# 07_LMS7002M_1_Power.net
KiCad netlist of a schematic drawn in Altium Designer
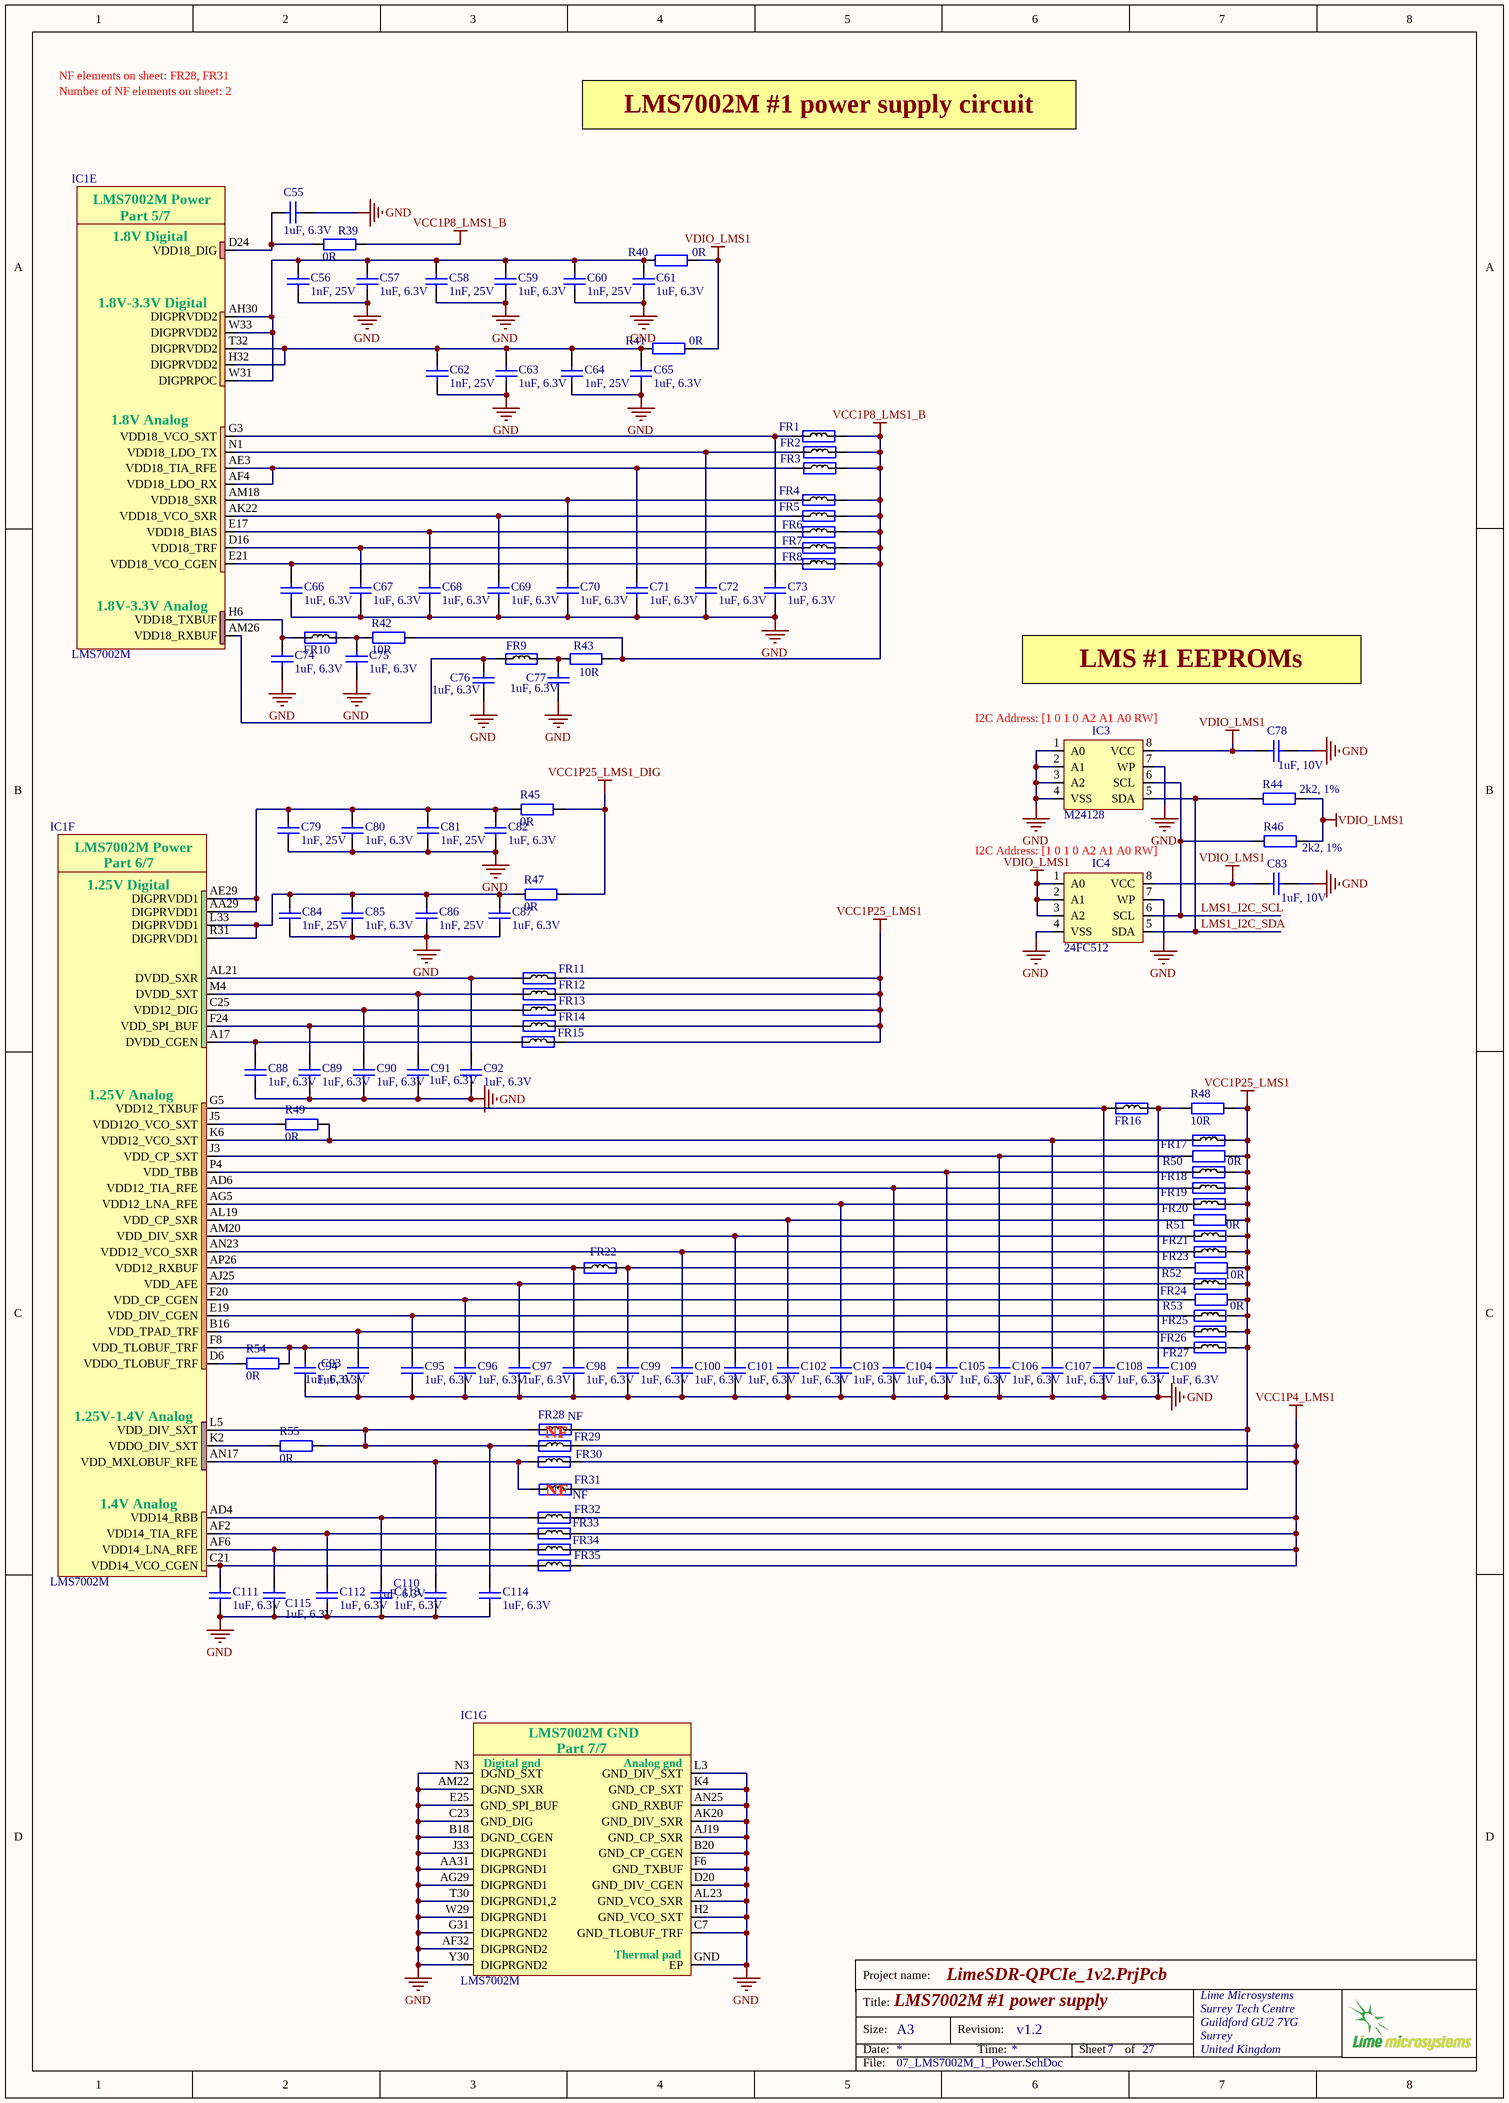
[diagram p0: 07_LMS7002M_1_Power.SchDoc]

(export (version "E")
  (design (tool "Eeschema 10.0.6"))
  (components
    (comp (ref "C55")
      (value "1uF, 6.3V")
      (footprint "CAP0201")
      (fields (field (name "TOLERANCE") "±20%") (field (name "MANUFACTURER") "TDK Corporation"))
      (libsource (lib "LimeMicroAltiumLib_schLib") (part "Cap_0402"))
    )
    (comp (ref "C56")
      (value "1nF, 25V")
      (footprint "CAP0201")
      (fields (field (name "TOLERANCE") "±10%") (field (name "MANUFACTURER") "TDK Corporation"))
      (libsource (lib "LimeMicroAltiumLib_schLib") (part "Cap_0402"))
    )
    (comp (ref "C57")
      (value "1uF, 6.3V")
      (footprint "CAP0201")
      (fields (field (name "TOLERANCE") "±20%") (field (name "MANUFACTURER") "TDK Corporation"))
      (libsource (lib "LimeMicroAltiumLib_schLib") (part "Cap_0402"))
    )
    (comp (ref "C58")
      (value "1nF, 25V")
      (footprint "CAP0201")
      (fields (field (name "TOLERANCE") "±10%") (field (name "MANUFACTURER") "TDK Corporation"))
      (libsource (lib "LimeMicroAltiumLib_schLib") (part "Cap_0402"))
    )
    (comp (ref "C59")
      (value "1uF, 6.3V")
      (footprint "CAP0201")
      (fields (field (name "TOLERANCE") "±20%") (field (name "MANUFACTURER") "TDK Corporation"))
      (libsource (lib "LimeMicroAltiumLib_schLib") (part "Cap_0402"))
    )
    (comp (ref "C60")
      (value "1nF, 25V")
      (footprint "CAP0201")
      (fields (field (name "TOLERANCE") "±10%") (field (name "MANUFACTURER") "TDK Corporation"))
      (libsource (lib "LimeMicroAltiumLib_schLib") (part "Cap_0402"))
    )
    (comp (ref "C61")
      (value "1uF, 6.3V")
      (footprint "CAP0201")
      (fields (field (name "TOLERANCE") "±20%") (field (name "MANUFACTURER") "TDK Corporation"))
      (libsource (lib "LimeMicroAltiumLib_schLib") (part "Cap_0402"))
    )
    (comp (ref "C62")
      (value "1nF, 25V")
      (footprint "CAP0201")
      (fields (field (name "TOLERANCE") "±10%") (field (name "MANUFACTURER") "TDK Corporation"))
      (libsource (lib "LimeMicroAltiumLib_schLib") (part "Cap_0402"))
    )
    (comp (ref "C63")
      (value "1uF, 6.3V")
      (footprint "CAP0201")
      (fields (field (name "TOLERANCE") "±20%") (field (name "MANUFACTURER") "TDK Corporation"))
      (libsource (lib "LimeMicroAltiumLib_schLib") (part "Cap_0402"))
    )
    (comp (ref "C64")
      (value "1nF, 25V")
      (footprint "CAP0201")
      (fields (field (name "TOLERANCE") "±10%") (field (name "MANUFACTURER") "TDK Corporation"))
      (libsource (lib "LimeMicroAltiumLib_schLib") (part "Cap_0402"))
    )
    (comp (ref "C65")
      (value "1uF, 6.3V")
      (footprint "CAP0201")
      (fields (field (name "TOLERANCE") "±20%") (field (name "MANUFACTURER") "TDK Corporation"))
      (libsource (lib "LimeMicroAltiumLib_schLib") (part "Cap_0402"))
    )
    (comp (ref "C66")
      (value "1uF, 6.3V")
      (footprint "CAP0201")
      (fields (field (name "TOLERANCE") "±20%") (field (name "MANUFACTURER") "TDK Corporation"))
      (libsource (lib "LimeMicroAltiumLib_schLib") (part "Cap_0402"))
    )
    (comp (ref "C67")
      (value "1uF, 6.3V")
      (footprint "CAP0201")
      (fields (field (name "TOLERANCE") "±20%") (field (name "MANUFACTURER") "TDK Corporation"))
      (libsource (lib "LimeMicroAltiumLib_schLib") (part "Cap_0402"))
    )
    (comp (ref "C68")
      (value "1uF, 6.3V")
      (footprint "CAP0201")
      (fields (field (name "TOLERANCE") "±20%") (field (name "MANUFACTURER") "TDK Corporation"))
      (libsource (lib "LimeMicroAltiumLib_schLib") (part "Cap_0402"))
    )
    (comp (ref "C69")
      (value "1uF, 6.3V")
      (footprint "CAP0201")
      (fields (field (name "TOLERANCE") "±20%") (field (name "MANUFACTURER") "TDK Corporation"))
      (libsource (lib "LimeMicroAltiumLib_schLib") (part "Cap_0402"))
    )
    (comp (ref "C70")
      (value "1uF, 6.3V")
      (footprint "CAP0201")
      (fields (field (name "TOLERANCE") "±20%") (field (name "MANUFACTURER") "TDK Corporation"))
      (libsource (lib "LimeMicroAltiumLib_schLib") (part "Cap_0402"))
    )
    (comp (ref "C71")
      (value "1uF, 6.3V")
      (footprint "CAP0201")
      (fields (field (name "TOLERANCE") "±20%") (field (name "MANUFACTURER") "TDK Corporation"))
      (libsource (lib "LimeMicroAltiumLib_schLib") (part "Cap_0402"))
    )
    (comp (ref "C72")
      (value "1uF, 6.3V")
      (footprint "CAP0201")
      (fields (field (name "TOLERANCE") "±20%") (field (name "MANUFACTURER") "TDK Corporation"))
      (libsource (lib "LimeMicroAltiumLib_schLib") (part "Cap_0402"))
    )
    (comp (ref "C73")
      (value "1uF, 6.3V")
      (footprint "CAP0201")
      (fields (field (name "TOLERANCE") "±20%") (field (name "MANUFACTURER") "TDK Corporation"))
      (libsource (lib "LimeMicroAltiumLib_schLib") (part "Cap_0402"))
    )
    (comp (ref "C74")
      (value "1uF, 6.3V")
      (footprint "CAP0201")
      (fields (field (name "TOLERANCE") "±20%") (field (name "MANUFACTURER") "TDK Corporation"))
      (libsource (lib "LimeMicroAltiumLib_schLib") (part "Cap_0402"))
    )
    (comp (ref "C75")
      (value "1uF, 6.3V")
      (footprint "CAP0201")
      (fields (field (name "TOLERANCE") "±20%") (field (name "MANUFACTURER") "TDK Corporation"))
      (libsource (lib "LimeMicroAltiumLib_schLib") (part "Cap_0402"))
    )
    (comp (ref "C76")
      (value "1uF, 6.3V")
      (footprint "CAP0201")
      (fields (field (name "TOLERANCE") "±20%") (field (name "MANUFACTURER") "TDK Corporation"))
      (libsource (lib "LimeMicroAltiumLib_schLib") (part "Cap_0402"))
    )
    (comp (ref "C77")
      (value "1uF, 6.3V")
      (footprint "CAP0201")
      (fields (field (name "TOLERANCE") "±20%") (field (name "MANUFACTURER") "TDK Corporation"))
      (libsource (lib "LimeMicroAltiumLib_schLib") (part "Cap_0402"))
    )
    (comp (ref "C78")
      (value "1uF, 10V")
      (footprint "CAP0402")
      (fields (field (name "MANUFACTURER") "TDK"))
      (libsource (lib "LimeMicroAltiumLib_schLib") (part "Cap_0402"))
    )
    (comp (ref "C79")
      (value "1nF, 25V")
      (footprint "CAP0201")
      (fields (field (name "TOLERANCE") "±10%") (field (name "MANUFACTURER") "TDK Corporation"))
      (libsource (lib "LimeMicroAltiumLib_schLib") (part "Cap_0402"))
    )
    (comp (ref "C80")
      (value "1uF, 6.3V")
      (footprint "CAP0201")
      (fields (field (name "TOLERANCE") "±20%") (field (name "MANUFACTURER") "TDK Corporation"))
      (libsource (lib "LimeMicroAltiumLib_schLib") (part "Cap_0402"))
    )
    (comp (ref "C81")
      (value "1nF, 25V")
      (footprint "CAP0201")
      (fields (field (name "TOLERANCE") "±10%") (field (name "MANUFACTURER") "TDK Corporation"))
      (libsource (lib "LimeMicroAltiumLib_schLib") (part "Cap_0402"))
    )
    (comp (ref "C82")
      (value "1uF, 6.3V")
      (footprint "CAP0201")
      (fields (field (name "TOLERANCE") "±20%") (field (name "MANUFACTURER") "TDK Corporation"))
      (libsource (lib "LimeMicroAltiumLib_schLib") (part "Cap_0402"))
    )
    (comp (ref "C83")
      (value "1uF, 10V")
      (footprint "CAP0402")
      (fields (field (name "MANUFACTURER") "TDK"))
      (libsource (lib "LimeMicroAltiumLib_schLib") (part "Cap_0402"))
    )
    (comp (ref "C84")
      (value "1nF, 25V")
      (footprint "CAP0201")
      (fields (field (name "TOLERANCE") "±10%") (field (name "MANUFACTURER") "TDK Corporation"))
      (libsource (lib "LimeMicroAltiumLib_schLib") (part "Cap_0402"))
    )
    (comp (ref "C85")
      (value "1uF, 6.3V")
      (footprint "CAP0201")
      (fields (field (name "TOLERANCE") "±20%") (field (name "MANUFACTURER") "TDK Corporation"))
      (libsource (lib "LimeMicroAltiumLib_schLib") (part "Cap_0402"))
    )
    (comp (ref "C86")
      (value "1nF, 25V")
      (footprint "CAP0201")
      (fields (field (name "TOLERANCE") "±10%") (field (name "MANUFACTURER") "TDK Corporation"))
      (libsource (lib "LimeMicroAltiumLib_schLib") (part "Cap_0402"))
    )
    (comp (ref "C87")
      (value "1uF, 6.3V")
      (footprint "CAP0201")
      (fields (field (name "TOLERANCE") "±20%") (field (name "MANUFACTURER") "TDK Corporation"))
      (libsource (lib "LimeMicroAltiumLib_schLib") (part "Cap_0402"))
    )
    (comp (ref "C88")
      (value "1uF, 6.3V")
      (footprint "CAP0201")
      (fields (field (name "TOLERANCE") "±20%") (field (name "MANUFACTURER") "TDK Corporation"))
      (libsource (lib "LimeMicroAltiumLib_schLib") (part "Cap_0402"))
    )
    (comp (ref "C89")
      (value "1uF, 6.3V")
      (footprint "CAP0201")
      (fields (field (name "TOLERANCE") "±20%") (field (name "MANUFACTURER") "TDK Corporation"))
      (libsource (lib "LimeMicroAltiumLib_schLib") (part "Cap_0402"))
    )
    (comp (ref "C90")
      (value "1uF, 6.3V")
      (footprint "CAP0201")
      (fields (field (name "TOLERANCE") "±20%") (field (name "MANUFACTURER") "TDK Corporation"))
      (libsource (lib "LimeMicroAltiumLib_schLib") (part "Cap_0402"))
    )
    (comp (ref "C91")
      (value "1uF, 6.3V")
      (footprint "CAP0201")
      (fields (field (name "TOLERANCE") "±20%") (field (name "MANUFACTURER") "TDK Corporation"))
      (libsource (lib "LimeMicroAltiumLib_schLib") (part "Cap_0402"))
    )
    (comp (ref "C92")
      (value "1uF, 6.3V")
      (footprint "CAP0201")
      (fields (field (name "TOLERANCE") "±20%") (field (name "MANUFACTURER") "TDK Corporation"))
      (libsource (lib "LimeMicroAltiumLib_schLib") (part "Cap_0402"))
    )
    (comp (ref "C93")
      (value "1uF, 6.3V")
      (footprint "CAP0201")
      (fields (field (name "TOLERANCE") "±20%") (field (name "MANUFACTURER") "TDK Corporation"))
      (libsource (lib "LimeMicroAltiumLib_schLib") (part "Cap_0402"))
    )
    (comp (ref "C94")
      (value "1uF, 6.3V")
      (footprint "CAP0201")
      (fields (field (name "TOLERANCE") "±20%") (field (name "MANUFACTURER") "TDK Corporation"))
      (libsource (lib "LimeMicroAltiumLib_schLib") (part "Cap_0402"))
    )
    (comp (ref "C95")
      (value "1uF, 6.3V")
      (footprint "CAP0201")
      (fields (field (name "TOLERANCE") "±20%") (field (name "MANUFACTURER") "TDK Corporation"))
      (libsource (lib "LimeMicroAltiumLib_schLib") (part "Cap_0402"))
    )
    (comp (ref "C96")
      (value "1uF, 6.3V")
      (footprint "CAP0201")
      (fields (field (name "TOLERANCE") "±20%") (field (name "MANUFACTURER") "TDK Corporation"))
      (libsource (lib "LimeMicroAltiumLib_schLib") (part "Cap_0402"))
    )
    (comp (ref "C97")
      (value "1uF, 6.3V")
      (footprint "CAP0201")
      (fields (field (name "TOLERANCE") "±20%") (field (name "MANUFACTURER") "TDK Corporation"))
      (libsource (lib "LimeMicroAltiumLib_schLib") (part "Cap_0402"))
    )
    (comp (ref "C98")
      (value "1uF, 6.3V")
      (footprint "CAP0201")
      (fields (field (name "TOLERANCE") "±20%") (field (name "MANUFACTURER") "TDK Corporation"))
      (libsource (lib "LimeMicroAltiumLib_schLib") (part "Cap_0402"))
    )
    (comp (ref "C99")
      (value "1uF, 6.3V")
      (footprint "CAP0201")
      (fields (field (name "TOLERANCE") "±20%") (field (name "MANUFACTURER") "TDK Corporation"))
      (libsource (lib "LimeMicroAltiumLib_schLib") (part "Cap_0402"))
    )
    (comp (ref "C100")
      (value "1uF, 6.3V")
      (footprint "CAP0201")
      (fields (field (name "TOLERANCE") "±20%") (field (name "MANUFACTURER") "TDK Corporation"))
      (libsource (lib "LimeMicroAltiumLib_schLib") (part "Cap_0402"))
    )
    (comp (ref "C101")
      (value "1uF, 6.3V")
      (footprint "CAP0201")
      (fields (field (name "TOLERANCE") "±20%") (field (name "MANUFACTURER") "TDK Corporation"))
      (libsource (lib "LimeMicroAltiumLib_schLib") (part "Cap_0402"))
    )
    (comp (ref "C102")
      (value "1uF, 6.3V")
      (footprint "CAP0201")
      (fields (field (name "TOLERANCE") "±20%") (field (name "MANUFACTURER") "TDK Corporation"))
      (libsource (lib "LimeMicroAltiumLib_schLib") (part "Cap_0402"))
    )
    (comp (ref "C103")
      (value "1uF, 6.3V")
      (footprint "CAP0201")
      (fields (field (name "TOLERANCE") "±20%") (field (name "MANUFACTURER") "TDK Corporation"))
      (libsource (lib "LimeMicroAltiumLib_schLib") (part "Cap_0402"))
    )
    (comp (ref "C104")
      (value "1uF, 6.3V")
      (footprint "CAP0201")
      (fields (field (name "TOLERANCE") "±20%") (field (name "MANUFACTURER") "TDK Corporation"))
      (libsource (lib "LimeMicroAltiumLib_schLib") (part "Cap_0402"))
    )
    (comp (ref "C105")
      (value "1uF, 6.3V")
      (footprint "CAP0201")
      (fields (field (name "TOLERANCE") "±20%") (field (name "MANUFACTURER") "TDK Corporation"))
      (libsource (lib "LimeMicroAltiumLib_schLib") (part "Cap_0402"))
    )
    (comp (ref "C106")
      (value "1uF, 6.3V")
      (footprint "CAP0201")
      (fields (field (name "TOLERANCE") "±20%") (field (name "MANUFACTURER") "TDK Corporation"))
      (libsource (lib "LimeMicroAltiumLib_schLib") (part "Cap_0402"))
    )
    (comp (ref "C107")
      (value "1uF, 6.3V")
      (footprint "CAP0201")
      (fields (field (name "TOLERANCE") "±20%") (field (name "MANUFACTURER") "TDK Corporation"))
      (libsource (lib "LimeMicroAltiumLib_schLib") (part "Cap_0402"))
    )
    (comp (ref "C108")
      (value "1uF, 6.3V")
      (footprint "CAP0201")
      (fields (field (name "TOLERANCE") "±20%") (field (name "MANUFACTURER") "TDK Corporation"))
      (libsource (lib "LimeMicroAltiumLib_schLib") (part "Cap_0402"))
    )
    (comp (ref "C109")
      (value "1uF, 6.3V")
      (footprint "CAP0201")
      (fields (field (name "TOLERANCE") "±20%") (field (name "MANUFACTURER") "TDK Corporation"))
      (libsource (lib "LimeMicroAltiumLib_schLib") (part "Cap_0402"))
    )
    (comp (ref "C110")
      (value "1uF, 6.3V")
      (footprint "CAP0201")
      (fields (field (name "TOLERANCE") "±20%") (field (name "MANUFACTURER") "TDK Corporation"))
      (libsource (lib "LimeMicroAltiumLib_schLib") (part "Cap_0402"))
    )
    (comp (ref "C111")
      (value "1uF, 6.3V")
      (footprint "CAP0201")
      (fields (field (name "TOLERANCE") "±20%") (field (name "MANUFACTURER") "TDK Corporation"))
      (libsource (lib "LimeMicroAltiumLib_schLib") (part "Cap_0402"))
    )
    (comp (ref "C112")
      (value "1uF, 6.3V")
      (footprint "CAP0201")
      (fields (field (name "TOLERANCE") "±20%") (field (name "MANUFACTURER") "TDK Corporation"))
      (libsource (lib "LimeMicroAltiumLib_schLib") (part "Cap_0402"))
    )
    (comp (ref "C113")
      (value "1uF, 6.3V")
      (footprint "CAP0201")
      (fields (field (name "TOLERANCE") "±20%") (field (name "MANUFACTURER") "TDK Corporation"))
      (libsource (lib "LimeMicroAltiumLib_schLib") (part "Cap_0402"))
    )
    (comp (ref "C114")
      (value "1uF, 6.3V")
      (footprint "CAP0201")
      (fields (field (name "TOLERANCE") "±20%") (field (name "MANUFACTURER") "TDK Corporation"))
      (libsource (lib "LimeMicroAltiumLib_schLib") (part "Cap_0402"))
    )
    (comp (ref "C115")
      (value "1uF, 6.3V")
      (footprint "CAP0201")
      (fields (field (name "TOLERANCE") "±20%") (field (name "MANUFACTURER") "TDK Corporation"))
      (libsource (lib "LimeMicroAltiumLib_schLib") (part "Cap_0402"))
    )
    (comp (ref "FR1")
      (value "Ferrite")
      (footprint "RES0201")
      (fields (field (name "MANUFACTURER") "Taiyo Yuden"))
      (libsource (lib "") (part "Ferrite_1"))
    )
    (comp (ref "FR2")
      (value "Ferrite")
      (footprint "RES0201")
      (fields (field (name "MANUFACTURER") "Taiyo Yuden"))
      (libsource (lib "LimeMicroAltiumLib_schLib") (part "Ferrite"))
    )
    (comp (ref "FR3")
      (value "Ferrite")
      (footprint "RES0201")
      (fields (field (name "MANUFACTURER") "Taiyo Yuden"))
      (libsource (lib "LimeMicroAltiumLib_schLib") (part "Ferrite"))
    )
    (comp (ref "FR4")
      (value "Ferrite")
      (footprint "RES0201")
      (fields (field (name "MANUFACTURER") "Taiyo Yuden"))
      (libsource (lib "") (part "Ferrite_1"))
    )
    (comp (ref "FR5")
      (value "Ferrite")
      (footprint "RES0201")
      (fields (field (name "MANUFACTURER") "Taiyo Yuden"))
      (libsource (lib "") (part "Ferrite_1"))
    )
    (comp (ref "FR6")
      (value "Ferrite")
      (footprint "RES0201")
      (fields (field (name "MANUFACTURER") "Taiyo Yuden"))
      (libsource (lib "") (part "Ferrite_1"))
    )
    (comp (ref "FR7")
      (value "Ferrite")
      (footprint "RES0201")
      (fields (field (name "MANUFACTURER") "Taiyo Yuden"))
      (libsource (lib "") (part "Ferrite_1"))
    )
    (comp (ref "FR8")
      (value "Ferrite")
      (footprint "RES0201")
      (fields (field (name "MANUFACTURER") "Taiyo Yuden"))
      (libsource (lib "") (part "Ferrite_1"))
    )
    (comp (ref "FR9")
      (value "Ferrite")
      (footprint "RES0201")
      (fields (field (name "MANUFACTURER") "Taiyo Yuden"))
      (libsource (lib "") (part "Ferrite_1"))
    )
    (comp (ref "FR10")
      (value "Ferrite")
      (footprint "RES0201")
      (fields (field (name "MANUFACTURER") "Taiyo Yuden"))
      (libsource (lib "LimeMicroAltiumLib_schLib") (part "Ferrite"))
    )
    (comp (ref "FR11")
      (value "Ferrite")
      (footprint "RES0201")
      (fields (field (name "MANUFACTURER") "Taiyo Yuden"))
      (libsource (lib "LimeMicroAltiumLib_schLib") (part "Ferrite"))
    )
    (comp (ref "FR12")
      (value "Ferrite")
      (footprint "RES0201")
      (fields (field (name "MANUFACTURER") "Taiyo Yuden"))
      (libsource (lib "LimeMicroAltiumLib_schLib") (part "Ferrite"))
    )
    (comp (ref "FR13")
      (value "Ferrite")
      (footprint "RES0201")
      (fields (field (name "MANUFACTURER") "Taiyo Yuden"))
      (libsource (lib "LimeMicroAltiumLib_schLib") (part "Ferrite"))
    )
    (comp (ref "FR14")
      (value "Ferrite")
      (footprint "RES0201")
      (fields (field (name "MANUFACTURER") "Taiyo Yuden"))
      (libsource (lib "LimeMicroAltiumLib_schLib") (part "Ferrite"))
    )
    (comp (ref "FR15")
      (value "Ferrite")
      (footprint "RES0201")
      (fields (field (name "MANUFACTURER") "Taiyo Yuden"))
      (libsource (lib "") (part "Ferrite_1"))
    )
    (comp (ref "FR16")
      (value "Ferrite")
      (footprint "RES0201")
      (fields (field (name "MANUFACTURER") "Taiyo Yuden"))
      (libsource (lib "LimeMicroAltiumLib_schLib") (part "Ferrite"))
    )
    (comp (ref "FR17")
      (value "Ferrite")
      (footprint "RES0201")
      (fields (field (name "MANUFACTURER") "Taiyo Yuden"))
      (libsource (lib "LimeMicroAltiumLib_schLib") (part "Ferrite"))
    )
    (comp (ref "FR18")
      (value "Ferrite")
      (footprint "RES0201")
      (fields (field (name "MANUFACTURER") "Taiyo Yuden"))
      (libsource (lib "LimeMicroAltiumLib_schLib") (part "Ferrite"))
    )
    (comp (ref "FR19")
      (value "Ferrite")
      (footprint "RES0201")
      (fields (field (name "MANUFACTURER") "Taiyo Yuden"))
      (libsource (lib "LimeMicroAltiumLib_schLib") (part "Ferrite"))
    )
    (comp (ref "FR20")
      (value "Ferrite")
      (footprint "RES0201")
      (fields (field (name "MANUFACTURER") "Taiyo Yuden"))
      (libsource (lib "LimeMicroAltiumLib_schLib") (part "Ferrite"))
    )
    (comp (ref "FR21")
      (value "Ferrite")
      (footprint "RES0201")
      (fields (field (name "MANUFACTURER") "Taiyo Yuden"))
      (libsource (lib "") (part "Ferrite_1"))
    )
    (comp (ref "FR22")
      (value "Ferrite")
      (footprint "RES0201")
      (fields (field (name "MANUFACTURER") "Taiyo Yuden"))
      (libsource (lib "") (part "Ferrite_1"))
    )
    (comp (ref "FR23")
      (value "Ferrite")
      (footprint "RES0201")
      (fields (field (name "MANUFACTURER") "Taiyo Yuden"))
      (libsource (lib "") (part "Ferrite_1"))
    )
    (comp (ref "FR24")
      (value "Ferrite")
      (footprint "RES0201")
      (fields (field (name "MANUFACTURER") "Taiyo Yuden"))
      (libsource (lib "") (part "Ferrite_1"))
    )
    (comp (ref "FR25")
      (value "Ferrite")
      (footprint "RES0201")
      (fields (field (name "MANUFACTURER") "Taiyo Yuden"))
      (libsource (lib "") (part "Ferrite_1"))
    )
    (comp (ref "FR26")
      (value "Ferrite")
      (footprint "RES0201")
      (fields (field (name "MANUFACTURER") "Taiyo Yuden"))
      (libsource (lib "") (part "Ferrite_1"))
    )
    (comp (ref "FR27")
      (value "Ferrite")
      (footprint "RES0201")
      (fields (field (name "MANUFACTURER") "Taiyo Yuden"))
      (libsource (lib "") (part "Ferrite_1"))
    )
    (comp (ref "FR28")
      (value "Ferrite")
      (footprint "RES0201")
      (fields (field (name "MANUFACTURER") "Taiyo Yuden") (field (name "ASSEMBLY INFO") "NF"))
      (libsource (lib "LimeMicroAltiumLib_schLib") (part "Ferrite"))
    )
    (comp (ref "FR29")
      (value "Ferrite")
      (footprint "RES0201")
      (fields (field (name "MANUFACTURER") "Taiyo Yuden"))
      (libsource (lib "LimeMicroAltiumLib_schLib") (part "Ferrite"))
    )
    (comp (ref "FR30")
      (value "Ferrite")
      (footprint "RES0201")
      (fields (field (name "MANUFACTURER") "Taiyo Yuden"))
      (libsource (lib "") (part "Ferrite_1"))
    )
    (comp (ref "FR31")
      (value "Ferrite")
      (footprint "RES0201")
      (fields (field (name "MANUFACTURER") "Taiyo Yuden") (field (name "ASSEMBLY INFO") "NF"))
      (libsource (lib "") (part "Ferrite_1"))
    )
    (comp (ref "FR32")
      (value "Ferrite")
      (footprint "RES0201")
      (fields (field (name "MANUFACTURER") "Taiyo Yuden"))
      (libsource (lib "") (part "Ferrite_1"))
    )
    (comp (ref "FR33")
      (value "Ferrite")
      (footprint "RES0201")
      (fields (field (name "MANUFACTURER") "Taiyo Yuden"))
      (libsource (lib "") (part "Ferrite_1"))
    )
    (comp (ref "FR34")
      (value "Ferrite")
      (footprint "RES0201")
      (fields (field (name "MANUFACTURER") "Taiyo Yuden"))
      (libsource (lib "") (part "Ferrite_1"))
    )
    (comp (ref "FR35")
      (value "Ferrite")
      (footprint "RES0201")
      (fields (field (name "MANUFACTURER") "Taiyo Yuden"))
      (libsource (lib "") (part "Ferrite_1"))
    )
    (comp (ref "IC1")
      (value "LMS7002M")
      (footprint "LMS7002M_v4")
      (description "Schematic symbol revision 3. Default footprint - 0.31mm pad")
      (fields (field (name "MANUFACTURER") "Lime Microsystems"))
      (libsource (lib "LimeMicroAltiumLib_schLib") (part "LMS7002Mr3"))
    )
    (comp (ref "IC3")
      (value "M24128")
      (footprint "24FC512")
      (fields (field (name "MANUFACTURER") "STMicroelectronics"))
      (libsource (lib "LimeMicroAltiumLib_schLib") (part "24FC64F"))
    )
    (comp (ref "IC4")
      (value "24FC512")
      (footprint "24FC512")
      (fields (field (name "MANUFACTURER") "Microchip Technology"))
      (libsource (lib "LimeMicroAltiumLib_schLib") (part "24FC512"))
    )
    (comp (ref "R39")
      (value "0R")
      (footprint "RES0201")
      (fields (field (name "MANUFACTURER") "Rohm Semiconductor") (field (name "TOLERANCE") "Jumper"))
      (libsource (lib "LimeMicroAltiumLib_schLib") (part "Res_0402"))
    )
    (comp (ref "R40")
      (value "0R")
      (footprint "RES0402")
      (fields (field (name "MANUFACTURER") "Yageo") (field (name "TOLERANCE") "Jumper"))
      (libsource (lib "LimeMicroAltiumLib_schLib") (part "Res_0402"))
    )
    (comp (ref "R41")
      (value "0R")
      (footprint "RES0402")
      (fields (field (name "MANUFACTURER") "Yageo") (field (name "TOLERANCE") "Jumper"))
      (libsource (lib "LimeMicroAltiumLib_schLib") (part "Res_0402"))
    )
    (comp (ref "R42")
      (value "10R")
      (footprint "RES0201")
      (fields
        (field (name "MANUFACTURER") "Panasonic Electronic Components")
        (field (name "TOLERANCE") "±1%")
      )
      (libsource (lib "LimeMicroAltiumLib_schLib") (part "Res_0402"))
    )
    (comp (ref "R43")
      (value "10R")
      (footprint "RES0201")
      (fields
        (field (name "MANUFACTURER") "Panasonic Electronic Components")
        (field (name "TOLERANCE") "±1%")
      )
      (libsource (lib "LimeMicroAltiumLib_schLib") (part "Res_0402"))
    )
    (comp (ref "R44")
      (value "2k2, 1%")
      (footprint "RES0402")
      (fields (field (name "MANUFACTURER") "Stackpole Electronics Inc") (field (name "TOLERANCE") "±1%"))
      (libsource (lib "LimeMicroAltiumLib_schLib") (part "Res_0402"))
    )
    (comp (ref "R45")
      (value "0R")
      (footprint "RES0402")
      (fields (field (name "MANUFACTURER") "Yageo") (field (name "TOLERANCE") "Jumper"))
      (libsource (lib "LimeMicroAltiumLib_schLib") (part "Res_0402"))
    )
    (comp (ref "R46")
      (value "2k2, 1%")
      (footprint "RES0402")
      (fields (field (name "MANUFACTURER") "Stackpole Electronics Inc") (field (name "TOLERANCE") "±1%"))
      (libsource (lib "LimeMicroAltiumLib_schLib") (part "Res_0402"))
    )
    (comp (ref "R47")
      (value "0R")
      (footprint "RES0402")
      (fields (field (name "MANUFACTURER") "Yageo") (field (name "TOLERANCE") "Jumper"))
      (libsource (lib "LimeMicroAltiumLib_schLib") (part "Res_0402"))
    )
    (comp (ref "R48")
      (value "10R")
      (footprint "RES0201")
      (fields
        (field (name "MANUFACTURER") "Panasonic Electronic Components")
        (field (name "TOLERANCE") "±1%")
      )
      (libsource (lib "LimeMicroAltiumLib_schLib") (part "Res_0402"))
    )
    (comp (ref "R49")
      (value "0R")
      (footprint "RES0201")
      (fields (field (name "MANUFACTURER") "Rohm Semiconductor") (field (name "TOLERANCE") "Jumper"))
      (libsource (lib "LimeMicroAltiumLib_schLib") (part "Res_0402"))
    )
    (comp (ref "R50")
      (value "0R")
      (footprint "RES0201")
      (fields (field (name "MANUFACTURER") "Rohm Semiconductor") (field (name "TOLERANCE") "Jumper"))
      (libsource (lib "LimeMicroAltiumLib_schLib") (part "Res_0402"))
    )
    (comp (ref "R51")
      (value "0R")
      (footprint "RES0201")
      (fields (field (name "MANUFACTURER") "Rohm Semiconductor") (field (name "TOLERANCE") "Jumper"))
      (libsource (lib "LimeMicroAltiumLib_schLib") (part "Res_0402"))
    )
    (comp (ref "R52")
      (value "10R")
      (footprint "RES0201")
      (fields
        (field (name "MANUFACTURER") "Panasonic Electronic Components")
        (field (name "TOLERANCE") "±1%")
      )
      (libsource (lib "LimeMicroAltiumLib_schLib") (part "Res_0402"))
    )
    (comp (ref "R53")
      (value "0R")
      (footprint "RES0201")
      (fields (field (name "MANUFACTURER") "Rohm Semiconductor") (field (name "TOLERANCE") "Jumper"))
      (libsource (lib "LimeMicroAltiumLib_schLib") (part "Res_0402"))
    )
    (comp (ref "R54")
      (value "0R")
      (footprint "RES0201")
      (fields (field (name "MANUFACTURER") "Rohm Semiconductor") (field (name "TOLERANCE") "Jumper"))
      (libsource (lib "LimeMicroAltiumLib_schLib") (part "Res_0402"))
    )
    (comp (ref "R55")
      (value "0R")
      (footprint "RES0201")
      (fields (field (name "MANUFACTURER") "Rohm Semiconductor") (field (name "TOLERANCE") "Jumper"))
      (libsource (lib "LimeMicroAltiumLib_schLib") (part "Res_0402"))
    )
  )
  (nets
    (net (code "1") (name "/LMS1_I2C_SCL") (class "Default")
      (node (ref "IC3") (pin "6") (pinfunction "SCL_6") (pintype "passive"))
      (node (ref "IC4") (pin "6") (pinfunction "SCL_6") (pintype "passive"))
      (node (ref "R46") (pin "2") (pinfunction "2_2") (pintype "passive"))
    )
    (net (code "2") (name "/LMS1_I2C_SDA") (class "Default")
      (node (ref "IC3") (pin "5") (pinfunction "SDA_5") (pintype "passive"))
      (node (ref "IC4") (pin "5") (pinfunction "SDA_5") (pintype "passive"))
      (node (ref "R44") (pin "2") (pinfunction "2_2") (pintype "passive"))
    )
    (net (code "3") (name "GND") (class "Default")
      (node (ref "C100") (pin "2") (pinfunction "2_2") (pintype "passive"))
      (node (ref "C101") (pin "2") (pinfunction "2_2") (pintype "passive"))
      (node (ref "C102") (pin "2") (pinfunction "2_2") (pintype "passive"))
      (node (ref "C103") (pin "2") (pinfunction "2_2") (pintype "passive"))
      (node (ref "C104") (pin "2") (pinfunction "2_2") (pintype "passive"))
      (node (ref "C105") (pin "2") (pinfunction "2_2") (pintype "passive"))
      (node (ref "C106") (pin "1") (pinfunction "1_1") (pintype "passive"))
      (node (ref "C107") (pin "1") (pinfunction "1_1") (pintype "passive"))
      (node (ref "C108") (pin "2") (pinfunction "2_2") (pintype "passive"))
      (node (ref "C109") (pin "2") (pinfunction "2_2") (pintype "passive"))
      (node (ref "C110") (pin "2") (pinfunction "2_2") (pintype "passive"))
      (node (ref "C111") (pin "2") (pinfunction "2_2") (pintype "passive"))
      (node (ref "C112") (pin "2") (pinfunction "2_2") (pintype "passive"))
      (node (ref "C113") (pin "2") (pinfunction "2_2") (pintype "passive"))
      (node (ref "C114") (pin "2") (pinfunction "2_2") (pintype "passive"))
      (node (ref "C115") (pin "2") (pinfunction "2_2") (pintype "passive"))
      (node (ref "C55") (pin "2") (pinfunction "2_2") (pintype "passive"))
      (node (ref "C56") (pin "2") (pinfunction "2_2") (pintype "passive"))
      (node (ref "C57") (pin "2") (pinfunction "2_2") (pintype "passive"))
      (node (ref "C58") (pin "2") (pinfunction "2_2") (pintype "passive"))
      (node (ref "C59") (pin "2") (pinfunction "2_2") (pintype "passive"))
      (node (ref "C60") (pin "2") (pinfunction "2_2") (pintype "passive"))
      (node (ref "C61") (pin "2") (pinfunction "2_2") (pintype "passive"))
      (node (ref "C62") (pin "2") (pinfunction "2_2") (pintype "passive"))
      (node (ref "C63") (pin "2") (pinfunction "2_2") (pintype "passive"))
      (node (ref "C64") (pin "2") (pinfunction "2_2") (pintype "passive"))
      (node (ref "C65") (pin "2") (pinfunction "2_2") (pintype "passive"))
      (node (ref "C66") (pin "2") (pinfunction "2_2") (pintype "passive"))
      (node (ref "C67") (pin "2") (pinfunction "2_2") (pintype "passive"))
      (node (ref "C68") (pin "2") (pinfunction "2_2") (pintype "passive"))
      (node (ref "C69") (pin "2") (pinfunction "2_2") (pintype "passive"))
      (node (ref "C70") (pin "2") (pinfunction "2_2") (pintype "passive"))
      (node (ref "C71") (pin "2") (pinfunction "2_2") (pintype "passive"))
      (node (ref "C72") (pin "2") (pinfunction "2_2") (pintype "passive"))
      (node (ref "C73") (pin "2") (pinfunction "2_2") (pintype "passive"))
      (node (ref "C74") (pin "2") (pinfunction "2_2") (pintype "passive"))
      (node (ref "C75") (pin "2") (pinfunction "2_2") (pintype "passive"))
      (node (ref "C76") (pin "2") (pinfunction "2_2") (pintype "passive"))
      (node (ref "C77") (pin "2") (pinfunction "2_2") (pintype "passive"))
      (node (ref "C78") (pin "1") (pinfunction "1_1") (pintype "passive"))
      (node (ref "C79") (pin "2") (pinfunction "2_2") (pintype "passive"))
      (node (ref "C80") (pin "2") (pinfunction "2_2") (pintype "passive"))
      (node (ref "C81") (pin "2") (pinfunction "2_2") (pintype "passive"))
      (node (ref "C82") (pin "2") (pinfunction "2_2") (pintype "passive"))
      (node (ref "C83") (pin "1") (pinfunction "1_1") (pintype "passive"))
      (node (ref "C84") (pin "2") (pinfunction "2_2") (pintype "passive"))
      (node (ref "C85") (pin "2") (pinfunction "2_2") (pintype "passive"))
      (node (ref "C86") (pin "2") (pinfunction "2_2") (pintype "passive"))
      (node (ref "C87") (pin "2") (pinfunction "2_2") (pintype "passive"))
      (node (ref "C88") (pin "2") (pinfunction "2_2") (pintype "passive"))
      (node (ref "C89") (pin "2") (pinfunction "2_2") (pintype "passive"))
      (node (ref "C90") (pin "2") (pinfunction "2_2") (pintype "passive"))
      (node (ref "C91") (pin "2") (pinfunction "2_2") (pintype "passive"))
      (node (ref "C92") (pin "2") (pinfunction "2_2") (pintype "passive"))
      (node (ref "C93") (pin "2") (pinfunction "2_2") (pintype "passive"))
      (node (ref "C94") (pin "2") (pinfunction "2_2") (pintype "passive"))
      (node (ref "C95") (pin "2") (pinfunction "2_2") (pintype "passive"))
      (node (ref "C96") (pin "2") (pinfunction "2_2") (pintype "passive"))
      (node (ref "C97") (pin "2") (pinfunction "2_2") (pintype "passive"))
      (node (ref "C98") (pin "2") (pinfunction "2_2") (pintype "passive"))
      (node (ref "C99") (pin "2") (pinfunction "2_2") (pintype "passive"))
      (node (ref "IC1") (pin "AA31") (pinfunction "DIGPRGND1_AA31") (pintype "passive"))
      (node (ref "IC1") (pin "AF32") (pinfunction "DIGPRGND2_AF32") (pintype "passive"))
      (node (ref "IC1") (pin "AG29") (pinfunction "DIGPRGND1_AG29") (pintype "passive"))
      (node (ref "IC1") (pin "AJ19") (pinfunction "GND_CP_SXR_AJ19") (pintype "passive"))
      (node (ref "IC1") (pin "AK20") (pinfunction "GND_DIV_SXR_AK20") (pintype "passive"))
      (node (ref "IC1") (pin "AL23") (pinfunction "GND_VCO_SXR_AL23") (pintype "passive"))
      (node (ref "IC1") (pin "AM22") (pinfunction "DGND_SXR_AM22") (pintype "passive"))
      (node (ref "IC1") (pin "AN25") (pinfunction "GND_RXBUF_AN25") (pintype "passive"))
      (node (ref "IC1") (pin "B18") (pinfunction "DGND_CGEN_B18") (pintype "passive"))
      (node (ref "IC1") (pin "B20") (pinfunction "GND_CP_CGEN_B20") (pintype "passive"))
      (node (ref "IC1") (pin "C23") (pinfunction "GND_DIG_C23") (pintype "passive"))
      (node (ref "IC1") (pin "C7") (pinfunction "GND_TLOBUF_TRF_C7") (pintype "passive"))
      (node (ref "IC1") (pin "D20") (pinfunction "GND_DIV_CGEN_D20") (pintype "passive"))
      (node (ref "IC1") (pin "E25") (pinfunction "GND_SPI_BUF_E25") (pintype "passive"))
      (node (ref "IC1") (pin "F6") (pinfunction "GND_TXBUF_F6") (pintype "passive"))
      (node (ref "IC1") (pin "G31") (pinfunction "DIGPRGND2_G31") (pintype "passive"))
      (node (ref "IC1") (pin "GND") (pinfunction "EP_GND") (pintype "passive"))
      (node (ref "IC1") (pin "H2") (pinfunction "GND_VCO_SXT_H2") (pintype "passive"))
      (node (ref "IC1") (pin "J33") (pinfunction "DIGPRGND1_J33") (pintype "passive"))
      (node (ref "IC1") (pin "K4") (pinfunction "GND_CP_SXT_K4") (pintype "passive"))
      (node (ref "IC1") (pin "L3") (pinfunction "GND_DIV_SXT_L3") (pintype "passive"))
      (node (ref "IC1") (pin "N3") (pinfunction "DGND_SXT_N3") (pintype "passive"))
      (node (ref "IC1") (pin "T30") (pinfunction "DIGPRGND1,2_T30") (pintype "passive"))
      (node (ref "IC1") (pin "W29") (pinfunction "DIGPRGND1_W29") (pintype "passive"))
      (node (ref "IC1") (pin "Y30") (pinfunction "DIGPRGND2_Y30") (pintype "passive"))
      (node (ref "IC3") (pin "1") (pinfunction "A0_1") (pintype "passive"))
      (node (ref "IC3") (pin "2") (pinfunction "A1_2") (pintype "passive"))
      (node (ref "IC3") (pin "3") (pinfunction "A2_3") (pintype "passive"))
      (node (ref "IC3") (pin "4") (pinfunction "VSS_4") (pintype "passive"))
      (node (ref "IC3") (pin "7") (pinfunction "WP_7") (pintype "passive"))
      (node (ref "IC4") (pin "4") (pinfunction "VSS_4") (pintype "passive"))
      (node (ref "IC4") (pin "7") (pinfunction "WP_7") (pintype "passive"))
    )
    (net (code "4") (name "Net-(C62-Pad1)") (class "Default")
      (node (ref "C62") (pin "1") (pinfunction "1_1") (pintype "passive"))
      (node (ref "C63") (pin "1") (pinfunction "1_1") (pintype "passive"))
      (node (ref "C64") (pin "1") (pinfunction "1_1") (pintype "passive"))
      (node (ref "C65") (pin "1") (pinfunction "1_1") (pintype "passive"))
      (node (ref "IC1") (pin "H32") (pinfunction "DIGPRVDD2_H32") (pintype "power_in"))
      (node (ref "IC1") (pin "T32") (pinfunction "DIGPRVDD2_T32") (pintype "power_in"))
      (node (ref "R41") (pin "2") (pinfunction "2_2") (pintype "passive"))
    )
    (net (code "5") (name "Net-(C75-Pad1)") (class "Default")
      (node (ref "C75") (pin "1") (pinfunction "1_1") (pintype "passive"))
      (node (ref "FR10") (pin "1") (pinfunction "1_1") (pintype "passive"))
      (node (ref "R42") (pin "1") (pinfunction "1_1") (pintype "passive"))
    )
    (net (code "6") (name "Net-(C77-Pad1)") (class "Default")
      (node (ref "C77") (pin "1") (pinfunction "1_1") (pintype "passive"))
      (node (ref "FR9") (pin "2") (pinfunction "2_2") (pintype "passive"))
      (node (ref "R43") (pin "2") (pinfunction "2_2") (pintype "passive"))
    )
    (net (code "7") (name "Net-(C79-Pad1)") (class "Default")
      (node (ref "C79") (pin "1") (pinfunction "1_1") (pintype "passive"))
      (node (ref "C80") (pin "1") (pinfunction "1_1") (pintype "passive"))
      (node (ref "C81") (pin "1") (pinfunction "1_1") (pintype "passive"))
      (node (ref "C82") (pin "1") (pinfunction "1_1") (pintype "passive"))
      (node (ref "IC1") (pin "AA29") (pinfunction "DIGPRVDD1_AA29") (pintype "power_in"))
      (node (ref "IC1") (pin "AE29") (pinfunction "DIGPRVDD1_AE29") (pintype "power_in"))
      (node (ref "R45") (pin "1") (pinfunction "1_1") (pintype "passive"))
    )
    (net (code "8") (name "Net-(C84-Pad1)") (class "Default")
      (node (ref "C84") (pin "1") (pinfunction "1_1") (pintype "passive"))
      (node (ref "C85") (pin "1") (pinfunction "1_1") (pintype "passive"))
      (node (ref "C86") (pin "1") (pinfunction "1_1") (pintype "passive"))
      (node (ref "C87") (pin "1") (pinfunction "1_1") (pintype "passive"))
      (node (ref "IC1") (pin "L33") (pinfunction "DIGPRVDD1_L33") (pintype "power_in"))
      (node (ref "IC1") (pin "R31") (pinfunction "DIGPRVDD1_R31") (pintype "power_in"))
      (node (ref "R47") (pin "1") (pinfunction "1_1") (pintype "passive"))
    )
    (net (code "9") (name "Net-(C99-Pad1)") (class "Default")
      (node (ref "C99") (pin "1") (pinfunction "1_1") (pintype "passive"))
      (node (ref "FR22") (pin "2") (pinfunction "2_2") (pintype "passive"))
      (node (ref "R52") (pin "2") (pinfunction "2_2") (pintype "passive"))
    )
    (net (code "10") (name "Net-(C109-Pad1)") (class "Default")
      (node (ref "C109") (pin "1") (pinfunction "1_1") (pintype "passive"))
      (node (ref "FR16") (pin "1") (pinfunction "1_1") (pintype "passive"))
      (node (ref "R48") (pin "1") (pinfunction "1_1") (pintype "passive"))
    )
    (net (code "11") (name "Net-(IC1E-DIGPRPOC)") (class "Default")
      (node (ref "C56") (pin "1") (pinfunction "1_1") (pintype "passive"))
      (node (ref "C57") (pin "1") (pinfunction "1_1") (pintype "passive"))
      (node (ref "C58") (pin "1") (pinfunction "1_1") (pintype "passive"))
      (node (ref "C59") (pin "1") (pinfunction "1_1") (pintype "passive"))
      (node (ref "C60") (pin "1") (pinfunction "1_1") (pintype "passive"))
      (node (ref "C61") (pin "1") (pinfunction "1_1") (pintype "passive"))
      (node (ref "IC1") (pin "AH30") (pinfunction "DIGPRVDD2_AH30") (pintype "power_in"))
      (node (ref "IC1") (pin "W31") (pinfunction "DIGPRPOC_W31") (pintype "power_in"))
      (node (ref "IC1") (pin "W33") (pinfunction "DIGPRVDD2_W33") (pintype "power_in"))
      (node (ref "R40") (pin "2") (pinfunction "2_2") (pintype "passive"))
    )
    (net (code "12") (name "Net-(IC1E-VDD18_BIAS)") (class "Default")
      (node (ref "C68") (pin "1") (pinfunction "1_1") (pintype "passive"))
      (node (ref "FR6") (pin "1") (pinfunction "1_1") (pintype "passive"))
      (node (ref "IC1") (pin "E17") (pinfunction "VDD18_BIAS_E17") (pintype "power_in"))
    )
    (net (code "13") (name "Net-(IC1E-VDD18_DIG)") (class "Default")
      (node (ref "C55") (pin "1") (pinfunction "1_1") (pintype "passive"))
      (node (ref "IC1") (pin "D24") (pinfunction "VDD18_DIG_D24") (pintype "power_in"))
      (node (ref "R39") (pin "1") (pinfunction "1_1") (pintype "passive"))
    )
    (net (code "14") (name "Net-(IC1E-VDD18_LDO_RX)") (class "Default")
      (node (ref "C71") (pin "1") (pinfunction "1_1") (pintype "passive"))
      (node (ref "FR3") (pin "2") (pinfunction "2_2") (pintype "passive"))
      (node (ref "IC1") (pin "AE3") (pinfunction "VDD18_TIA_RFE_AE3") (pintype "power_in"))
      (node (ref "IC1") (pin "AF4") (pinfunction "VDD18_LDO_RX_AF4") (pintype "power_in"))
    )
    (net (code "15") (name "Net-(IC1E-VDD18_LDO_TX)") (class "Default")
      (node (ref "C72") (pin "1") (pinfunction "1_1") (pintype "passive"))
      (node (ref "FR2") (pin "2") (pinfunction "2_2") (pintype "passive"))
      (node (ref "IC1") (pin "N1") (pinfunction "VDD18_LDO_TX_N1") (pintype "power_in"))
    )
    (net (code "16") (name "Net-(IC1E-VDD18_RXBUF)") (class "Default")
      (node (ref "C76") (pin "1") (pinfunction "1_1") (pintype "passive"))
      (node (ref "FR9") (pin "1") (pinfunction "1_1") (pintype "passive"))
      (node (ref "IC1") (pin "AM26") (pinfunction "VDD18_RXBUF_AM26") (pintype "power_in"))
    )
    (net (code "17") (name "Net-(IC1E-VDD18_SXR)") (class "Default")
      (node (ref "C70") (pin "1") (pinfunction "1_1") (pintype "passive"))
      (node (ref "FR4") (pin "1") (pinfunction "1_1") (pintype "passive"))
      (node (ref "IC1") (pin "AM18") (pinfunction "VDD18_SXR_AM18") (pintype "power_in"))
    )
    (net (code "18") (name "Net-(IC1E-VDD18_TRF)") (class "Default")
      (node (ref "C67") (pin "1") (pinfunction "1_1") (pintype "passive"))
      (node (ref "FR7") (pin "1") (pinfunction "1_1") (pintype "passive"))
      (node (ref "IC1") (pin "D16") (pinfunction "VDD18_TRF_D16") (pintype "power_in"))
    )
    (net (code "19") (name "Net-(IC1E-VDD18_TXBUF)") (class "Default")
      (node (ref "C74") (pin "1") (pinfunction "1_1") (pintype "passive"))
      (node (ref "FR10") (pin "2") (pinfunction "2_2") (pintype "passive"))
      (node (ref "IC1") (pin "H6") (pinfunction "VDD18_TXBUF_H6") (pintype "power_in"))
    )
    (net (code "20") (name "Net-(IC1E-VDD18_VCO_CGEN)") (class "Default")
      (node (ref "C66") (pin "1") (pinfunction "1_1") (pintype "passive"))
      (node (ref "FR8") (pin "1") (pinfunction "1_1") (pintype "passive"))
      (node (ref "IC1") (pin "E21") (pinfunction "VDD18_VCO_CGEN_E21") (pintype "power_in"))
    )
    (net (code "21") (name "Net-(IC1E-VDD18_VCO_SXR)") (class "Default")
      (node (ref "C69") (pin "1") (pinfunction "1_1") (pintype "passive"))
      (node (ref "FR5") (pin "1") (pinfunction "1_1") (pintype "passive"))
      (node (ref "IC1") (pin "AK22") (pinfunction "VDD18_VCO_SXR_AK22") (pintype "power_in"))
    )
    (net (code "22") (name "Net-(IC1E-VDD18_VCO_SXT)") (class "Default")
      (node (ref "C73") (pin "1") (pinfunction "1_1") (pintype "passive"))
      (node (ref "FR1") (pin "1") (pinfunction "1_1") (pintype "passive"))
      (node (ref "IC1") (pin "G3") (pinfunction "VDD18_VCO_SXT_G3") (pintype "power_in"))
    )
    (net (code "23") (name "Net-(IC1F-DVDD_CGEN)") (class "Default")
      (node (ref "C88") (pin "1") (pinfunction "1_1") (pintype "passive"))
      (node (ref "FR15") (pin "1") (pinfunction "1_1") (pintype "passive"))
      (node (ref "IC1") (pin "A17") (pinfunction "DVDD_CGEN_A17") (pintype "power_in"))
    )
    (net (code "24") (name "Net-(IC1F-DVDD_SXR)") (class "Default")
      (node (ref "C92") (pin "1") (pinfunction "1_1") (pintype "passive"))
      (node (ref "FR11") (pin "2") (pinfunction "2_2") (pintype "passive"))
      (node (ref "IC1") (pin "AL21") (pinfunction "DVDD_SXR_AL21") (pintype "power_in"))
    )
    (net (code "25") (name "Net-(IC1F-DVDD_SXT)") (class "Default")
      (node (ref "C91") (pin "1") (pinfunction "1_1") (pintype "passive"))
      (node (ref "FR12") (pin "2") (pinfunction "2_2") (pintype "passive"))
      (node (ref "IC1") (pin "M4") (pinfunction "DVDD_SXT_M4") (pintype "power_in"))
    )
    (net (code "26") (name "Net-(IC1F-VDD12O_VCO_SXT)") (class "Default")
      (node (ref "IC1") (pin "J5") (pinfunction "VDD12O_VCO_SXT_J5") (pintype "power_in"))
      (node (ref "R49") (pin "1") (pinfunction "1_1") (pintype "passive"))
    )
    (net (code "27") (name "Net-(IC1F-VDD12_DIG)") (class "Default")
      (node (ref "C90") (pin "1") (pinfunction "1_1") (pintype "passive"))
      (node (ref "FR13") (pin "2") (pinfunction "2_2") (pintype "passive"))
      (node (ref "IC1") (pin "C25") (pinfunction "VDD12_DIG_C25") (pintype "power_in"))
    )
    (net (code "28") (name "Net-(IC1F-VDD12_LNA_RFE)") (class "Default")
      (node (ref "C103") (pin "1") (pinfunction "1_1") (pintype "passive"))
      (node (ref "FR20") (pin "2") (pinfunction "2_2") (pintype "passive"))
      (node (ref "IC1") (pin "AG5") (pinfunction "VDD12_LNA_RFE_AG5") (pintype "power_in"))
    )
    (net (code "29") (name "Net-(IC1F-VDD12_RXBUF)") (class "Default")
      (node (ref "C98") (pin "1") (pinfunction "1_1") (pintype "passive"))
      (node (ref "FR22") (pin "1") (pinfunction "1_1") (pintype "passive"))
      (node (ref "IC1") (pin "AP26") (pinfunction "VDD12_RXBUF_AP26") (pintype "power_in"))
    )
    (net (code "30") (name "Net-(IC1F-VDD12_TIA_RFE)") (class "Default")
      (node (ref "C104") (pin "1") (pinfunction "1_1") (pintype "passive"))
      (node (ref "FR19") (pin "2") (pinfunction "2_2") (pintype "passive"))
      (node (ref "IC1") (pin "AD6") (pinfunction "VDD12_TIA_RFE_AD6") (pintype "power_in"))
    )
    (net (code "31") (name "Net-(IC1F-VDD12_TXBUF)") (class "Default")
      (node (ref "C108") (pin "1") (pinfunction "1_1") (pintype "passive"))
      (node (ref "FR16") (pin "2") (pinfunction "2_2") (pintype "passive"))
      (node (ref "IC1") (pin "G5") (pinfunction "VDD12_TXBUF_G5") (pintype "power_in"))
    )
    (net (code "32") (name "Net-(IC1F-VDD12_VCO_SXR)") (class "Default")
      (node (ref "C100") (pin "1") (pinfunction "1_1") (pintype "passive"))
      (node (ref "FR23") (pin "1") (pinfunction "1_1") (pintype "passive"))
      (node (ref "IC1") (pin "AN23") (pinfunction "VDD12_VCO_SXR_AN23") (pintype "power_in"))
    )
    (net (code "33") (name "Net-(IC1F-VDD12_VCO_SXT)") (class "Default")
      (node (ref "C107") (pin "2") (pinfunction "2_2") (pintype "passive"))
      (node (ref "FR17") (pin "2") (pinfunction "2_2") (pintype "passive"))
      (node (ref "IC1") (pin "K6") (pinfunction "VDD12_VCO_SXT_K6") (pintype "power_in"))
      (node (ref "R49") (pin "2") (pinfunction "2_2") (pintype "passive"))
    )
    (net (code "34") (name "Net-(IC1F-VDD14_LNA_RFE)") (class "Default")
      (node (ref "C115") (pin "1") (pinfunction "1_1") (pintype "passive"))
      (node (ref "FR34") (pin "1") (pinfunction "1_1") (pintype "passive"))
      (node (ref "IC1") (pin "AF6") (pinfunction "VDD14_LNA_RFE_AF6") (pintype "power_in"))
    )
    (net (code "35") (name "Net-(IC1F-VDD14_RBB)") (class "Default")
      (node (ref "C113") (pin "1") (pinfunction "1_1") (pintype "passive"))
      (node (ref "FR32") (pin "1") (pinfunction "1_1") (pintype "passive"))
      (node (ref "IC1") (pin "AD4") (pinfunction "VDD14_RBB_AD4") (pintype "power_in"))
    )
    (net (code "36") (name "Net-(IC1F-VDD14_TIA_RFE)") (class "Default")
      (node (ref "C112") (pin "1") (pinfunction "1_1") (pintype "passive"))
      (node (ref "FR33") (pin "1") (pinfunction "1_1") (pintype "passive"))
      (node (ref "IC1") (pin "AF2") (pinfunction "VDD14_TIA_RFE_AF2") (pintype "power_in"))
    )
    (net (code "37") (name "Net-(IC1F-VDD14_VCO_CGEN)") (class "Default")
      (node (ref "C111") (pin "1") (pinfunction "1_1") (pintype "passive"))
      (node (ref "FR35") (pin "1") (pinfunction "1_1") (pintype "passive"))
      (node (ref "IC1") (pin "C21") (pinfunction "VDD14_VCO_CGEN_C21") (pintype "power_in"))
    )
    (net (code "38") (name "Net-(IC1F-VDDO_DIV_SXT)") (class "Default")
      (node (ref "IC1") (pin "K2") (pinfunction "VDDO_DIV_SXT_K2") (pintype "power_in"))
      (node (ref "R55") (pin "1") (pinfunction "1_1") (pintype "passive"))
    )
    (net (code "39") (name "Net-(IC1F-VDDO_TLOBUF_TRF)") (class "Default")
      (node (ref "IC1") (pin "D6") (pinfunction "VDDO_TLOBUF_TRF_D6") (pintype "power_in"))
      (node (ref "R54") (pin "2") (pinfunction "2_2") (pintype "passive"))
    )
    (net (code "40") (name "Net-(IC1F-VDD_AFE)") (class "Default")
      (node (ref "C97") (pin "1") (pinfunction "1_1") (pintype "passive"))
      (node (ref "FR24") (pin "1") (pinfunction "1_1") (pintype "passive"))
      (node (ref "IC1") (pin "AJ25") (pinfunction "VDD_AFE_AJ25") (pintype "power_in"))
    )
    (net (code "41") (name "Net-(IC1F-VDD_CP_CGEN)") (class "Default")
      (node (ref "C96") (pin "1") (pinfunction "1_1") (pintype "passive"))
      (node (ref "IC1") (pin "F20") (pinfunction "VDD_CP_CGEN_F20") (pintype "power_in"))
      (node (ref "R53") (pin "2") (pinfunction "2_2") (pintype "passive"))
    )
    (net (code "42") (name "Net-(IC1F-VDD_CP_SXR)") (class "Default")
      (node (ref "C102") (pin "1") (pinfunction "1_1") (pintype "passive"))
      (node (ref "IC1") (pin "AL19") (pinfunction "VDD_CP_SXR_AL19") (pintype "power_in"))
      (node (ref "R51") (pin "2") (pinfunction "2_2") (pintype "passive"))
    )
    (net (code "43") (name "Net-(IC1F-VDD_CP_SXT)") (class "Default")
      (node (ref "C106") (pin "2") (pinfunction "2_2") (pintype "passive"))
      (node (ref "IC1") (pin "J3") (pinfunction "VDD_CP_SXT_J3") (pintype "power_in"))
      (node (ref "R50") (pin "1") (pinfunction "1_1") (pintype "passive"))
    )
    (net (code "44") (name "Net-(IC1F-VDD_DIV_CGEN)") (class "Default")
      (node (ref "C95") (pin "1") (pinfunction "1_1") (pintype "passive"))
      (node (ref "FR25") (pin "1") (pinfunction "1_1") (pintype "passive"))
      (node (ref "IC1") (pin "E19") (pinfunction "VDD_DIV_CGEN_E19") (pintype "power_in"))
    )
    (net (code "45") (name "Net-(IC1F-VDD_DIV_SXR)") (class "Default")
      (node (ref "C101") (pin "1") (pinfunction "1_1") (pintype "passive"))
      (node (ref "FR21") (pin "1") (pinfunction "1_1") (pintype "passive"))
      (node (ref "IC1") (pin "AM20") (pinfunction "VDD_DIV_SXR_AM20") (pintype "power_in"))
    )
    (net (code "46") (name "Net-(IC1F-VDD_DIV_SXT)") (class "Default")
      (node (ref "C114") (pin "1") (pinfunction "1_1") (pintype "passive"))
      (node (ref "FR28") (pin "2") (pinfunction "2_2") (pintype "passive"))
      (node (ref "FR29") (pin "2") (pinfunction "2_2") (pintype "passive"))
      (node (ref "IC1") (pin "L5") (pinfunction "VDD_DIV_SXT_L5") (pintype "power_in"))
      (node (ref "R55") (pin "2") (pinfunction "2_2") (pintype "passive"))
    )
    (net (code "47") (name "Net-(IC1F-VDD_MXLOBUF_RFE)") (class "Default")
      (node (ref "C110") (pin "1") (pinfunction "1_1") (pintype "passive"))
      (node (ref "FR30") (pin "1") (pinfunction "1_1") (pintype "passive"))
      (node (ref "FR31") (pin "1") (pinfunction "1_1") (pintype "passive"))
      (node (ref "IC1") (pin "AN17") (pinfunction "VDD_MXLOBUF_RFE_AN17") (pintype "power_in"))
    )
    (net (code "48") (name "Net-(IC1F-VDD_SPI_BUF)") (class "Default")
      (node (ref "C89") (pin "1") (pinfunction "1_1") (pintype "passive"))
      (node (ref "FR14") (pin "2") (pinfunction "2_2") (pintype "passive"))
      (node (ref "IC1") (pin "F24") (pinfunction "VDD_SPI_BUF_F24") (pintype "power_in"))
    )
    (net (code "49") (name "Net-(IC1F-VDD_TBB)") (class "Default")
      (node (ref "C105") (pin "1") (pinfunction "1_1") (pintype "passive"))
      (node (ref "FR18") (pin "2") (pinfunction "2_2") (pintype "passive"))
      (node (ref "IC1") (pin "P4") (pinfunction "VDD_TBB_P4") (pintype "power_in"))
    )
    (net (code "50") (name "Net-(IC1F-VDD_TLOBUF_TRF)") (class "Default")
      (node (ref "C94") (pin "1") (pinfunction "1_1") (pintype "passive"))
      (node (ref "FR27") (pin "1") (pinfunction "1_1") (pintype "passive"))
      (node (ref "IC1") (pin "F8") (pinfunction "VDD_TLOBUF_TRF_F8") (pintype "power_in"))
      (node (ref "R54") (pin "1") (pinfunction "1_1") (pintype "passive"))
    )
    (net (code "51") (name "Net-(IC1F-VDD_TPAD_TRF)") (class "Default")
      (node (ref "C93") (pin "1") (pinfunction "1_1") (pintype "passive"))
      (node (ref "FR26") (pin "1") (pinfunction "1_1") (pintype "passive"))
      (node (ref "IC1") (pin "B16") (pinfunction "VDD_TPAD_TRF_B16") (pintype "power_in"))
    )
    (net (code "52") (name "VCC1P4_LMS1") (class "Default")
      (node (ref "FR29") (pin "1") (pinfunction "1_1") (pintype "passive"))
      (node (ref "FR30") (pin "2") (pinfunction "2_2") (pintype "passive"))
      (node (ref "FR32") (pin "2") (pinfunction "2_2") (pintype "passive"))
      (node (ref "FR33") (pin "2") (pinfunction "2_2") (pintype "passive"))
      (node (ref "FR34") (pin "2") (pinfunction "2_2") (pintype "passive"))
      (node (ref "FR35") (pin "2") (pinfunction "2_2") (pintype "passive"))
    )
    (net (code "53") (name "VCC1P8_LMS1_B") (class "Default")
      (node (ref "FR1") (pin "2") (pinfunction "2_2") (pintype "passive"))
      (node (ref "FR2") (pin "1") (pinfunction "1_1") (pintype "passive"))
      (node (ref "FR3") (pin "1") (pinfunction "1_1") (pintype "passive"))
      (node (ref "FR4") (pin "2") (pinfunction "2_2") (pintype "passive"))
      (node (ref "FR5") (pin "2") (pinfunction "2_2") (pintype "passive"))
      (node (ref "FR6") (pin "2") (pinfunction "2_2") (pintype "passive"))
      (node (ref "FR7") (pin "2") (pinfunction "2_2") (pintype "passive"))
      (node (ref "FR8") (pin "2") (pinfunction "2_2") (pintype "passive"))
      (node (ref "R39") (pin "2") (pinfunction "2_2") (pintype "passive"))
      (node (ref "R42") (pin "2") (pinfunction "2_2") (pintype "passive"))
      (node (ref "R43") (pin "1") (pinfunction "1_1") (pintype "passive"))
    )
    (net (code "54") (name "VCC1P25_LMS1") (class "Default")
      (node (ref "FR11") (pin "1") (pinfunction "1_1") (pintype "passive"))
      (node (ref "FR12") (pin "1") (pinfunction "1_1") (pintype "passive"))
      (node (ref "FR13") (pin "1") (pinfunction "1_1") (pintype "passive"))
      (node (ref "FR14") (pin "1") (pinfunction "1_1") (pintype "passive"))
      (node (ref "FR15") (pin "2") (pinfunction "2_2") (pintype "passive"))
      (node (ref "FR17") (pin "1") (pinfunction "1_1") (pintype "passive"))
      (node (ref "FR18") (pin "1") (pinfunction "1_1") (pintype "passive"))
      (node (ref "FR19") (pin "1") (pinfunction "1_1") (pintype "passive"))
      (node (ref "FR20") (pin "1") (pinfunction "1_1") (pintype "passive"))
      (node (ref "FR21") (pin "2") (pinfunction "2_2") (pintype "passive"))
      (node (ref "FR23") (pin "2") (pinfunction "2_2") (pintype "passive"))
      (node (ref "FR24") (pin "2") (pinfunction "2_2") (pintype "passive"))
      (node (ref "FR25") (pin "2") (pinfunction "2_2") (pintype "passive"))
      (node (ref "FR26") (pin "2") (pinfunction "2_2") (pintype "passive"))
      (node (ref "FR27") (pin "2") (pinfunction "2_2") (pintype "passive"))
      (node (ref "FR28") (pin "1") (pinfunction "1_1") (pintype "passive"))
      (node (ref "FR31") (pin "2") (pinfunction "2_2") (pintype "passive"))
      (node (ref "R48") (pin "2") (pinfunction "2_2") (pintype "passive"))
      (node (ref "R50") (pin "2") (pinfunction "2_2") (pintype "passive"))
      (node (ref "R51") (pin "1") (pinfunction "1_1") (pintype "passive"))
      (node (ref "R52") (pin "1") (pinfunction "1_1") (pintype "passive"))
      (node (ref "R53") (pin "1") (pinfunction "1_1") (pintype "passive"))
    )
    (net (code "55") (name "VCC1P25_LMS1_DIG") (class "Default")
      (node (ref "R45") (pin "2") (pinfunction "2_2") (pintype "passive"))
      (node (ref "R47") (pin "2") (pinfunction "2_2") (pintype "passive"))
    )
    (net (code "56") (name "VDIO_LMS1") (class "Default")
      (node (ref "C78") (pin "2") (pinfunction "2_2") (pintype "passive"))
      (node (ref "C83") (pin "2") (pinfunction "2_2") (pintype "passive"))
      (node (ref "IC3") (pin "8") (pinfunction "VCC_8") (pintype "passive"))
      (node (ref "IC4") (pin "1") (pinfunction "A0_1") (pintype "passive"))
      (node (ref "IC4") (pin "2") (pinfunction "A1_2") (pintype "passive"))
      (node (ref "IC4") (pin "3") (pinfunction "A2_3") (pintype "passive"))
      (node (ref "IC4") (pin "8") (pinfunction "VCC_8") (pintype "passive"))
      (node (ref "R40") (pin "1") (pinfunction "1_1") (pintype "passive"))
      (node (ref "R41") (pin "1") (pinfunction "1_1") (pintype "passive"))
      (node (ref "R44") (pin "1") (pinfunction "1_1") (pintype "passive"))
      (node (ref "R46") (pin "1") (pinfunction "1_1") (pintype "passive"))
    )
  )
)
